# K0N16_Keypad_v1_1.net
KiCad netlist of a schematic drawn in EAGLE
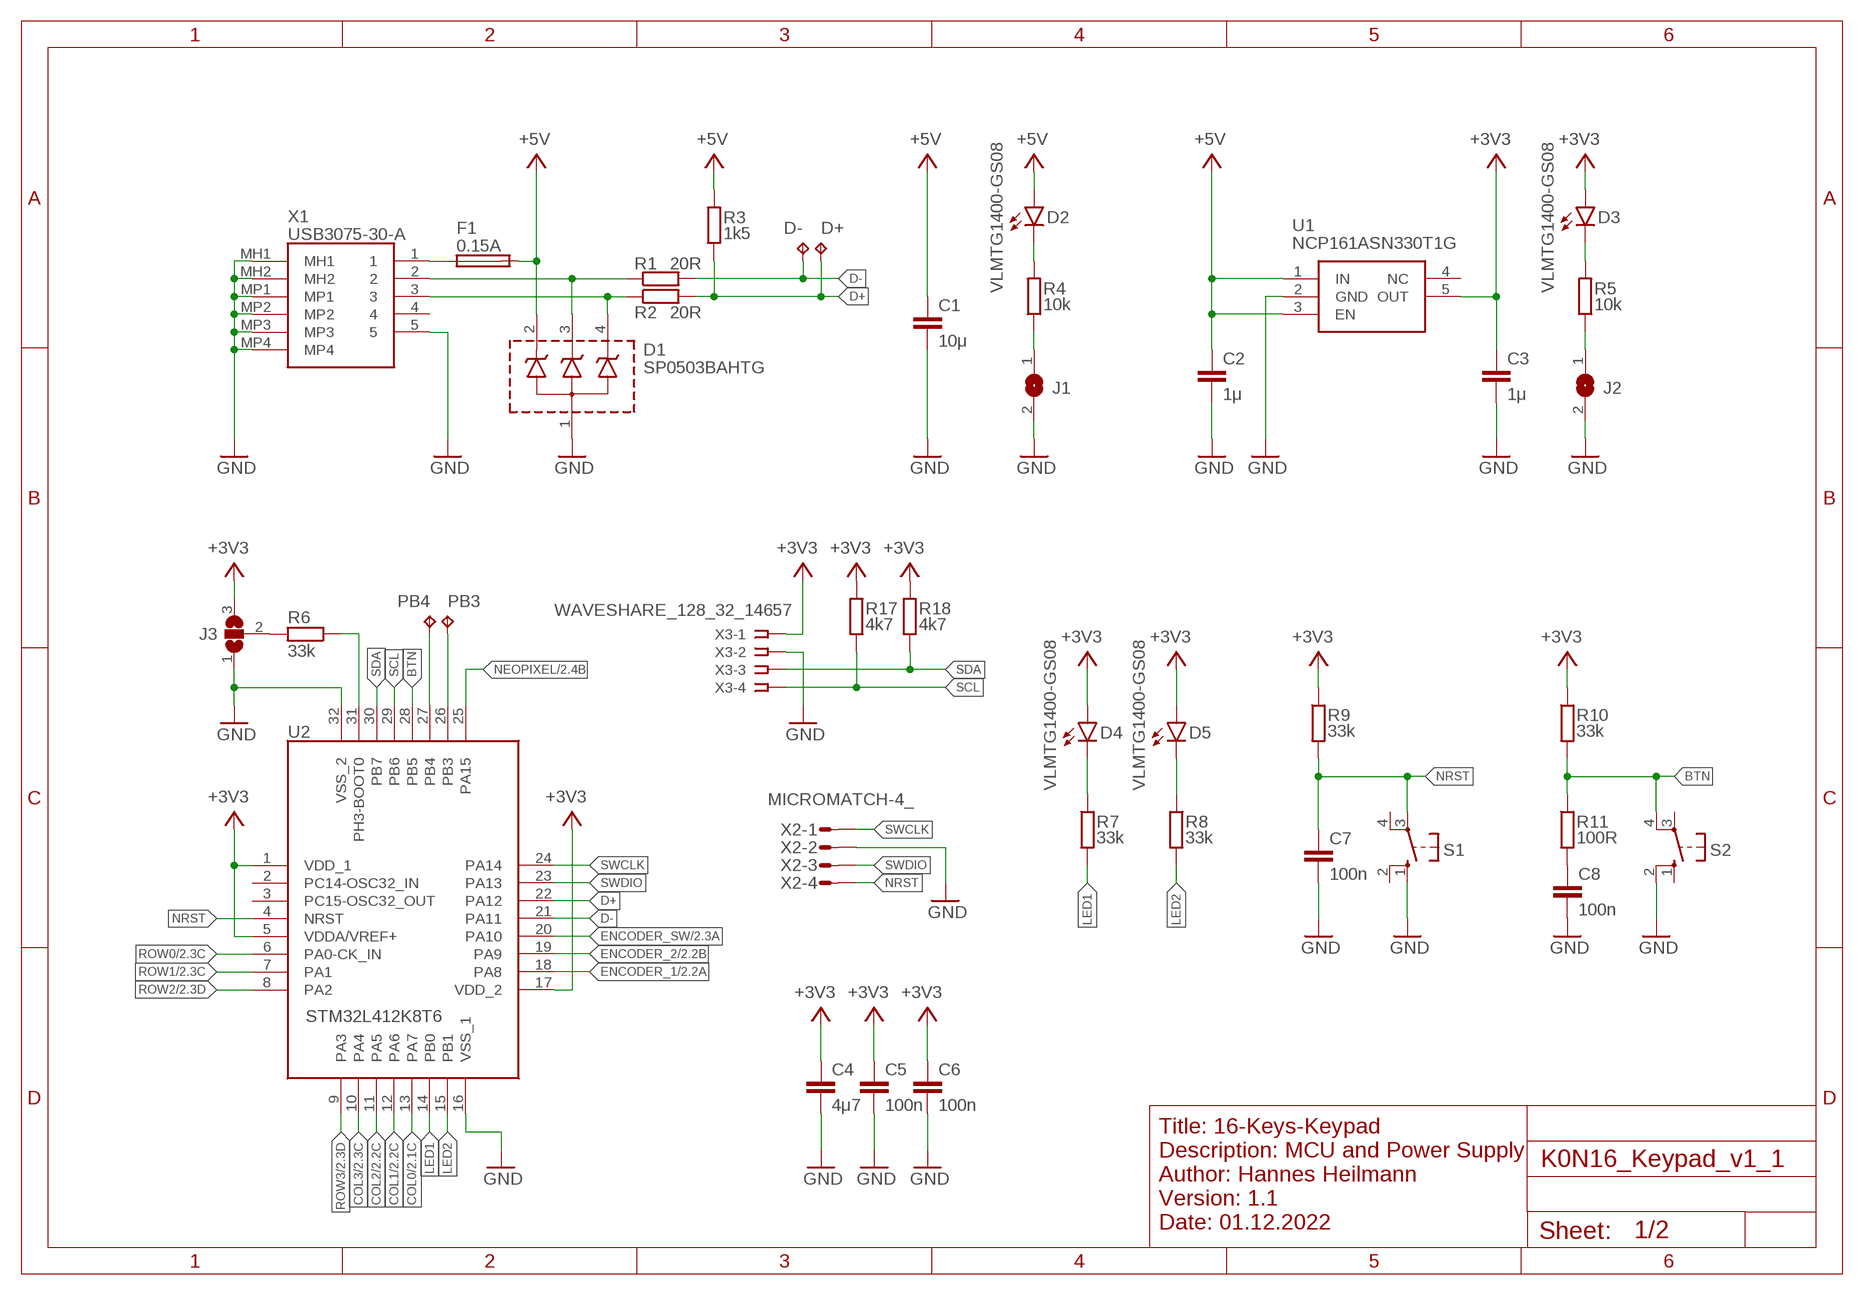
[diagram p0: schematic, sheet 1]
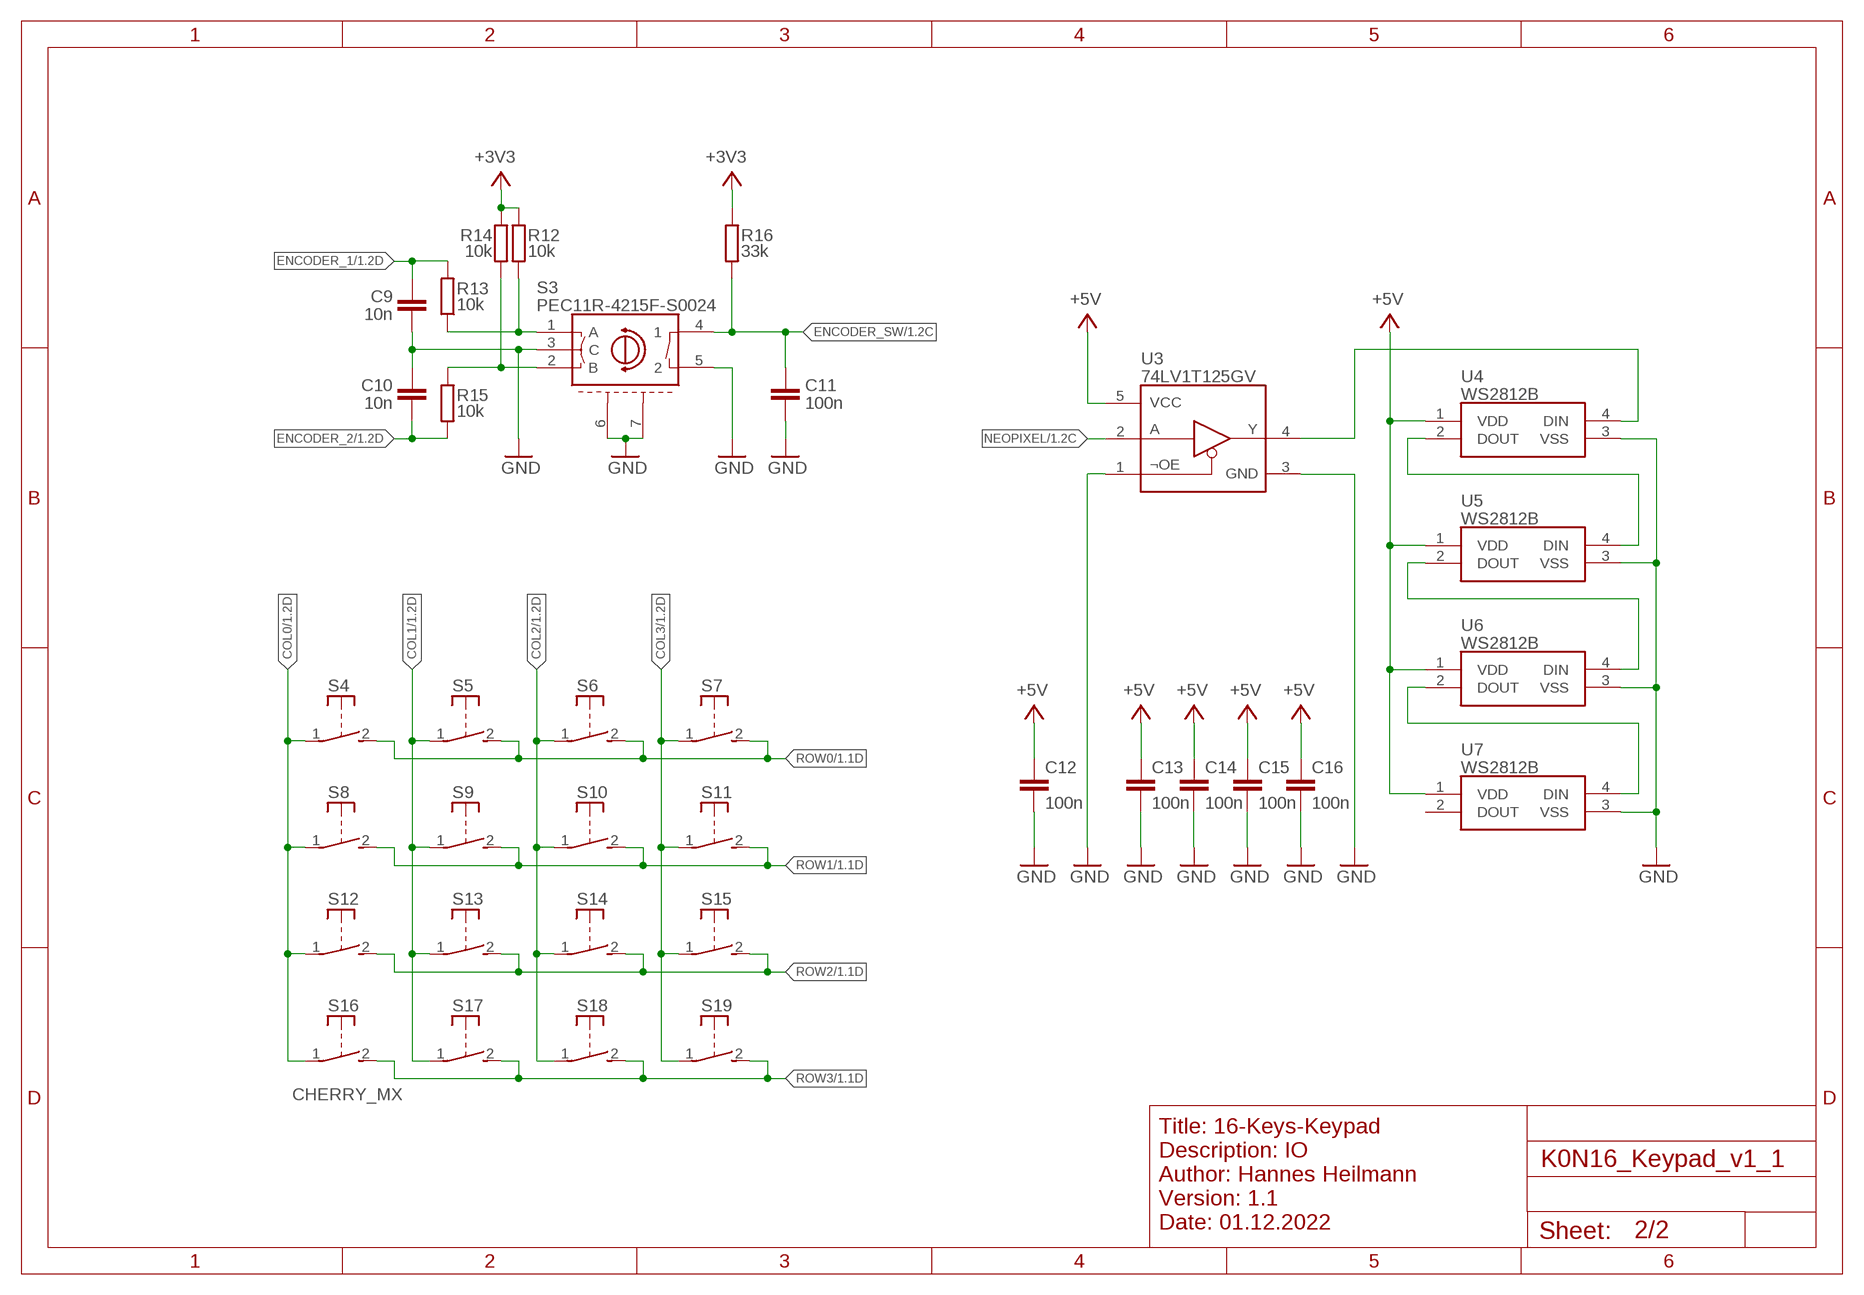
[diagram p1: schematic, sheet 2]

(export (version "E")
  (design (tool "Eeschema 10.0.6"))
  (components
    (comp (ref "C1")
      (value "10μ")
      (footprint "eagle-import:C1206")
      (libsource (lib "eagle-import") (part "C_1206C1206"))
    )
    (comp (ref "C2")
      (value "1μ")
      (footprint "eagle-import:C0805")
      (libsource (lib "eagle-import") (part "C_0805"))
    )
    (comp (ref "C3")
      (value "1μ")
      (footprint "eagle-import:C0805")
      (libsource (lib "eagle-import") (part "C_0805"))
    )
    (comp (ref "C4")
      (value "4μ7")
      (footprint "eagle-import:C0805")
      (libsource (lib "eagle-import") (part "C_0805"))
    )
    (comp (ref "C5")
      (value "100n")
      (footprint "eagle-import:C0805")
      (libsource (lib "eagle-import") (part "C_0805"))
    )
    (comp (ref "C6")
      (value "100n")
      (footprint "eagle-import:C0805")
      (libsource (lib "eagle-import") (part "C_0805"))
    )
    (comp (ref "C7")
      (value "100n")
      (footprint "eagle-import:C0805")
      (libsource (lib "eagle-import") (part "C_0805"))
    )
    (comp (ref "C8")
      (value "100n")
      (footprint "eagle-import:C0805")
      (libsource (lib "eagle-import") (part "C_0805"))
    )
    (comp (ref "D+")
      (value "TPB1,27")
      (footprint "eagle-import:B1,27")
      (libsource (lib "eagle-import") (part "TPB1,27"))
    )
    (comp (ref "D-")
      (value "TPB1,27")
      (footprint "eagle-import:B1,27")
      (libsource (lib "eagle-import") (part "TPB1,27"))
    )
    (comp (ref "D1")
      (value "SP0503BAHTG")
      (footprint "eagle-import:SP0503BAHTG")
      (fields (field (name "MOUSER_PART_NUMBER") "576-SP0503BAHTG"))
      (libsource (lib "eagle-import") (part "SP0503BAHTG"))
    )
    (comp (ref "D2")
      (value "VLMTG1400-GS08")
      (footprint "eagle-import:CHIP-LED0805")
      (libsource (lib "eagle-import") (part "LED_0805"))
    )
    (comp (ref "D3")
      (value "VLMTG1400-GS08")
      (footprint "eagle-import:CHIP-LED0805")
      (libsource (lib "eagle-import") (part "LED_0805"))
    )
    (comp (ref "D4")
      (value "VLMTG1400-GS08")
      (footprint "eagle-import:CHIP-LED0805")
      (libsource (lib "eagle-import") (part "LED_0805"))
    )
    (comp (ref "D5")
      (value "VLMTG1400-GS08")
      (footprint "eagle-import:CHIP-LED0805")
      (libsource (lib "eagle-import") (part "LED_0805"))
    )
    (comp (ref "F1")
      (value "FUSE_0603R0603")
      (footprint "eagle-import:R0603")
      (libsource (lib "eagle-import") (part "FUSE_0603R0603"))
    )
    (comp (ref "J1") (value "SJ") (footprint "eagle-import:SJ") (libsource (lib "eagle-import") (part "SJ")))
    (comp (ref "J2") (value "SJ") (footprint "eagle-import:SJ") (libsource (lib "eagle-import") (part "SJ")))
    (comp (ref "J3")
      (value "SJ2W")
      (footprint "eagle-import:SJ_2")
      (libsource (lib "eagle-import") (part "SJ2W"))
    )
    (comp (ref "PB3")
      (value "TPB1,27")
      (footprint "eagle-import:B1,27")
      (libsource (lib "eagle-import") (part "TPB1,27"))
    )
    (comp (ref "PB4")
      (value "TPB1,27")
      (footprint "eagle-import:B1,27")
      (libsource (lib "eagle-import") (part "TPB1,27"))
    )
    (comp (ref "R1")
      (value "20R")
      (footprint "eagle-import:R0805")
      (libsource (lib "eagle-import") (part "R_0805"))
    )
    (comp (ref "R2")
      (value "20R")
      (footprint "eagle-import:R0805")
      (libsource (lib "eagle-import") (part "R_0805"))
    )
    (comp (ref "R3")
      (value "1k5")
      (footprint "eagle-import:R0805")
      (libsource (lib "eagle-import") (part "R_0805"))
    )
    (comp (ref "R4")
      (value "10k")
      (footprint "eagle-import:R0805")
      (libsource (lib "eagle-import") (part "R_0805"))
    )
    (comp (ref "R5")
      (value "10k")
      (footprint "eagle-import:R0805")
      (libsource (lib "eagle-import") (part "R_0805"))
    )
    (comp (ref "R6")
      (value "33k")
      (footprint "eagle-import:R0805")
      (libsource (lib "eagle-import") (part "R_0805"))
    )
    (comp (ref "R7")
      (value "33k")
      (footprint "eagle-import:R0805")
      (libsource (lib "eagle-import") (part "R_0805"))
    )
    (comp (ref "R8")
      (value "33k")
      (footprint "eagle-import:R0805")
      (libsource (lib "eagle-import") (part "R_0805"))
    )
    (comp (ref "R9")
      (value "33k")
      (footprint "eagle-import:R0805")
      (libsource (lib "eagle-import") (part "R_0805"))
    )
    (comp (ref "R10")
      (value "33k")
      (footprint "eagle-import:R0805")
      (libsource (lib "eagle-import") (part "R_0805"))
    )
    (comp (ref "R11")
      (value "100R")
      (footprint "eagle-import:R0805")
      (libsource (lib "eagle-import") (part "R_0805"))
    )
    (comp (ref "R17")
      (value "4k7")
      (footprint "eagle-import:R0805")
      (libsource (lib "eagle-import") (part "R_0805"))
    )
    (comp (ref "R18")
      (value "4k7")
      (footprint "eagle-import:R0805")
      (libsource (lib "eagle-import") (part "R_0805"))
    )
    (comp (ref "S1")
      (value "10-XXB3F_10XX")
      (footprint "eagle-import:B3F-10XX")
      (libsource (lib "eagle-import") (part "10-XXB3F_10XX"))
    )
    (comp (ref "S2")
      (value "10-XXB3F_10XX")
      (footprint "eagle-import:B3F-10XX")
      (libsource (lib "eagle-import") (part "10-XXB3F_10XX"))
    )
    (comp (ref "U1")
      (value "NCP161ASN330T1G")
      (footprint "eagle-import:SOT95P280X145-5N")
      (fields (field (name "MOUSER_PART_NUMBER") "863-NCP161ASN330T1G"))
      (libsource (lib "eagle-import") (part "NCP161ASN330T1G"))
    )
    (comp (ref "U2")
      (value "STM32L412K8T6")
      (footprint "eagle-import:QFP80P900X900X160-32N")
      (fields (field (name "MOUSER_PART_NUMBER") "511-STM32L412K8T6"))
      (libsource (lib "eagle-import") (part "STM32L412K8T6"))
    )
    (comp (ref "X1")
      (value "USB3075-30-A")
      (footprint "eagle-import:USB307530A")
      (fields (field (name "MOUSER_PART_NUMBER") "640-USB3075-30-A"))
      (libsource (lib "eagle-import") (part "USB3075-30-A"))
    )
    (comp (ref "X2")
      (value "MICROMATCH-4_")
      (footprint "eagle-import:MICROMATCH-4")
      (libsource (lib "eagle-import") (part "MICROMATCH-4_"))
    )
    (comp (ref "X3")
      (value "WAVESHARE_128_32_14657")
      (footprint "eagle-import:SSW-104-02-G-S")
      (fields (field (name "MF") "Samtec Inc.") (field (name "MPN") "SSW-104-02-G-S"))
      (libsource (lib "eagle-import") (part "WAVESHARE_128_32_14657"))
    )
    (comp (ref "C9")
      (value "10n")
      (footprint "eagle-import:C0805")
      (libsource (lib "eagle-import") (part "C_0805"))
    )
    (comp (ref "C10")
      (value "10n")
      (footprint "eagle-import:C0805")
      (libsource (lib "eagle-import") (part "C_0805"))
    )
    (comp (ref "C11")
      (value "100n")
      (footprint "eagle-import:C0805")
      (libsource (lib "eagle-import") (part "C_0805"))
    )
    (comp (ref "C12")
      (value "100n")
      (footprint "eagle-import:C0805")
      (libsource (lib "eagle-import") (part "C_0805"))
    )
    (comp (ref "C13")
      (value "100n")
      (footprint "eagle-import:C0805")
      (libsource (lib "eagle-import") (part "C_0805"))
    )
    (comp (ref "C14")
      (value "100n")
      (footprint "eagle-import:C0805")
      (libsource (lib "eagle-import") (part "C_0805"))
    )
    (comp (ref "C15")
      (value "100n")
      (footprint "eagle-import:C0805")
      (libsource (lib "eagle-import") (part "C_0805"))
    )
    (comp (ref "C16")
      (value "100n")
      (footprint "eagle-import:C0805")
      (libsource (lib "eagle-import") (part "C_0805"))
    )
    (comp (ref "R12")
      (value "10k")
      (footprint "eagle-import:R0805")
      (libsource (lib "eagle-import") (part "R_0805"))
    )
    (comp (ref "R13")
      (value "10k")
      (footprint "eagle-import:R0805")
      (libsource (lib "eagle-import") (part "R_0805"))
    )
    (comp (ref "R14")
      (value "10k")
      (footprint "eagle-import:R0805")
      (libsource (lib "eagle-import") (part "R_0805"))
    )
    (comp (ref "R15")
      (value "10k")
      (footprint "eagle-import:R0805")
      (libsource (lib "eagle-import") (part "R_0805"))
    )
    (comp (ref "R16")
      (value "33k")
      (footprint "eagle-import:R0805")
      (libsource (lib "eagle-import") (part "R_0805"))
    )
    (comp (ref "S3")
      (value "PEC11R-4215F-S0024")
      (footprint "eagle-import:PEC12R-4XXXF-SXXXX_1")
      (fields
        (field (name "ARROW_PART_NUMBER") "PEC11R-4225F-S0024")
        (field (name "MOUSER_PART_NUMBER") "652-PEC11R-4225F-S24")
      )
      (libsource (lib "eagle-import") (part "PEC11R-4215F-S0024"))
    )
    (comp (ref "S4")
      (value "CHERRY_MX")
      (footprint "eagle-import:CHERRY_MX")
      (fields
        (field (name "ARROW_PART_NUMBER") "MX1A-E1NW")
        (field (name "MOUSER_PART_NUMBER") "540-MX1A-E1NW")
      )
      (libsource (lib "eagle-import") (part "CHERRY_MX"))
    )
    (comp (ref "S5")
      (value "CHERRY_MX")
      (footprint "eagle-import:CHERRY_MX")
      (fields
        (field (name "ARROW_PART_NUMBER") "MX1A-E1NW")
        (field (name "MOUSER_PART_NUMBER") "540-MX1A-E1NW")
      )
      (libsource (lib "eagle-import") (part "CHERRY_MX"))
    )
    (comp (ref "S6")
      (value "CHERRY_MX")
      (footprint "eagle-import:CHERRY_MX")
      (fields
        (field (name "ARROW_PART_NUMBER") "MX1A-E1NW")
        (field (name "MOUSER_PART_NUMBER") "540-MX1A-E1NW")
      )
      (libsource (lib "eagle-import") (part "CHERRY_MX"))
    )
    (comp (ref "S7")
      (value "CHERRY_MX")
      (footprint "eagle-import:CHERRY_MX")
      (fields
        (field (name "ARROW_PART_NUMBER") "MX1A-E1NW")
        (field (name "MOUSER_PART_NUMBER") "540-MX1A-E1NW")
      )
      (libsource (lib "eagle-import") (part "CHERRY_MX"))
    )
    (comp (ref "S8")
      (value "CHERRY_MX")
      (footprint "eagle-import:CHERRY_MX")
      (fields
        (field (name "ARROW_PART_NUMBER") "MX1A-E1NW")
        (field (name "MOUSER_PART_NUMBER") "540-MX1A-E1NW")
      )
      (libsource (lib "eagle-import") (part "CHERRY_MX"))
    )
    (comp (ref "S9")
      (value "CHERRY_MX")
      (footprint "eagle-import:CHERRY_MX")
      (fields
        (field (name "ARROW_PART_NUMBER") "MX1A-E1NW")
        (field (name "MOUSER_PART_NUMBER") "540-MX1A-E1NW")
      )
      (libsource (lib "eagle-import") (part "CHERRY_MX"))
    )
    (comp (ref "S10")
      (value "CHERRY_MX")
      (footprint "eagle-import:CHERRY_MX")
      (fields
        (field (name "ARROW_PART_NUMBER") "MX1A-E1NW")
        (field (name "MOUSER_PART_NUMBER") "540-MX1A-E1NW")
      )
      (libsource (lib "eagle-import") (part "CHERRY_MX"))
    )
    (comp (ref "S11")
      (value "CHERRY_MX")
      (footprint "eagle-import:CHERRY_MX")
      (fields
        (field (name "ARROW_PART_NUMBER") "MX1A-E1NW")
        (field (name "MOUSER_PART_NUMBER") "540-MX1A-E1NW")
      )
      (libsource (lib "eagle-import") (part "CHERRY_MX"))
    )
    (comp (ref "S12")
      (value "CHERRY_MX")
      (footprint "eagle-import:CHERRY_MX")
      (fields
        (field (name "ARROW_PART_NUMBER") "MX1A-E1NW")
        (field (name "MOUSER_PART_NUMBER") "540-MX1A-E1NW")
      )
      (libsource (lib "eagle-import") (part "CHERRY_MX"))
    )
    (comp (ref "S13")
      (value "CHERRY_MX")
      (footprint "eagle-import:CHERRY_MX")
      (fields
        (field (name "ARROW_PART_NUMBER") "MX1A-E1NW")
        (field (name "MOUSER_PART_NUMBER") "540-MX1A-E1NW")
      )
      (libsource (lib "eagle-import") (part "CHERRY_MX"))
    )
    (comp (ref "S14")
      (value "CHERRY_MX")
      (footprint "eagle-import:CHERRY_MX")
      (fields
        (field (name "ARROW_PART_NUMBER") "MX1A-E1NW")
        (field (name "MOUSER_PART_NUMBER") "540-MX1A-E1NW")
      )
      (libsource (lib "eagle-import") (part "CHERRY_MX"))
    )
    (comp (ref "S15")
      (value "CHERRY_MX")
      (footprint "eagle-import:CHERRY_MX")
      (fields
        (field (name "ARROW_PART_NUMBER") "MX1A-E1NW")
        (field (name "MOUSER_PART_NUMBER") "540-MX1A-E1NW")
      )
      (libsource (lib "eagle-import") (part "CHERRY_MX"))
    )
    (comp (ref "S16")
      (value "CHERRY_MX")
      (footprint "eagle-import:CHERRY_MX")
      (fields
        (field (name "ARROW_PART_NUMBER") "MX1A-E1NW")
        (field (name "MOUSER_PART_NUMBER") "540-MX1A-E1NW")
      )
      (libsource (lib "eagle-import") (part "CHERRY_MX"))
    )
    (comp (ref "S17")
      (value "CHERRY_MX")
      (footprint "eagle-import:CHERRY_MX")
      (fields
        (field (name "ARROW_PART_NUMBER") "MX1A-E1NW")
        (field (name "MOUSER_PART_NUMBER") "540-MX1A-E1NW")
      )
      (libsource (lib "eagle-import") (part "CHERRY_MX"))
    )
    (comp (ref "S18")
      (value "CHERRY_MX")
      (footprint "eagle-import:CHERRY_MX")
      (fields
        (field (name "ARROW_PART_NUMBER") "MX1A-E1NW")
        (field (name "MOUSER_PART_NUMBER") "540-MX1A-E1NW")
      )
      (libsource (lib "eagle-import") (part "CHERRY_MX"))
    )
    (comp (ref "S19")
      (value "CHERRY_MX")
      (footprint "eagle-import:CHERRY_MX")
      (fields
        (field (name "ARROW_PART_NUMBER") "MX1A-E1NW")
        (field (name "MOUSER_PART_NUMBER") "540-MX1A-E1NW")
      )
      (libsource (lib "eagle-import") (part "CHERRY_MX"))
    )
    (comp (ref "U3")
      (value "74LV1T125GV_")
      (footprint "eagle-import:SOT753")
      (libsource (lib "eagle-import") (part "74LV1T125GV_"))
    )
    (comp (ref "U4")
      (value "WS2812B")
      (footprint "eagle-import:WS2812B")
      (libsource (lib "eagle-import") (part "WS2812B"))
    )
    (comp (ref "U5")
      (value "WS2812B")
      (footprint "eagle-import:WS2812B")
      (libsource (lib "eagle-import") (part "WS2812B"))
    )
    (comp (ref "U6")
      (value "WS2812B")
      (footprint "eagle-import:WS2812B")
      (libsource (lib "eagle-import") (part "WS2812B"))
    )
    (comp (ref "U7")
      (value "WS2812B")
      (footprint "eagle-import:WS2812B")
      (libsource (lib "eagle-import") (part "WS2812B"))
    )
  )
  (nets
    (net (code "1") (name "+3V3") (class "Default")
      (node (ref "C3") (pin "1") (pinfunction "1_1") (pintype "passive"))
      (node (ref "C4") (pin "1") (pinfunction "1_1") (pintype "passive"))
      (node (ref "C5") (pin "1") (pinfunction "1_1") (pintype "passive"))
      (node (ref "C6") (pin "1") (pinfunction "1_1") (pintype "passive"))
      (node (ref "D3") (pin "A") (pinfunction "A_A") (pintype "passive"))
      (node (ref "D4") (pin "A") (pinfunction "A_A") (pintype "passive"))
      (node (ref "D5") (pin "A") (pinfunction "A_A") (pintype "passive"))
      (node (ref "J3") (pin "3") (pinfunction "3_3") (pintype "passive"))
      (node (ref "R10") (pin "1") (pinfunction "1_1") (pintype "passive"))
      (node (ref "R12") (pin "1") (pinfunction "1_1") (pintype "passive"))
      (node (ref "R14") (pin "1") (pinfunction "1_1") (pintype "passive"))
      (node (ref "R16") (pin "1") (pinfunction "1_1") (pintype "passive"))
      (node (ref "R17") (pin "1") (pinfunction "1_1") (pintype "passive"))
      (node (ref "R18") (pin "1") (pinfunction "1_1") (pintype "passive"))
      (node (ref "R9") (pin "1") (pinfunction "1_1") (pintype "passive"))
      (node (ref "U1") (pin "5") (pinfunction "OUT_5") (pintype "bidirectional"))
      (node (ref "U2") (pin "1") (pinfunction "VDD_1_1") (pintype "bidirectional"))
      (node (ref "U2") (pin "17") (pinfunction "VDD_2_17") (pintype "bidirectional"))
      (node (ref "U2") (pin "5") (pinfunction "VDDA/VREF+_5") (pintype "bidirectional"))
      (node (ref "X3") (pin "1") (pinfunction "1_1") (pintype "passive"))
    )
    (net (code "2") (name "+5V") (class "Default")
      (node (ref "C1") (pin "1") (pinfunction "1_1") (pintype "passive"))
      (node (ref "C12") (pin "1") (pinfunction "1_1") (pintype "passive"))
      (node (ref "C13") (pin "1") (pinfunction "1_1") (pintype "passive"))
      (node (ref "C14") (pin "1") (pinfunction "1_1") (pintype "passive"))
      (node (ref "C15") (pin "1") (pinfunction "1_1") (pintype "passive"))
      (node (ref "C16") (pin "1") (pinfunction "1_1") (pintype "passive"))
      (node (ref "C2") (pin "1") (pinfunction "1_1") (pintype "passive"))
      (node (ref "D1") (pin "2") (pinfunction "K_1_2") (pintype "bidirectional"))
      (node (ref "D2") (pin "A") (pinfunction "A_A") (pintype "passive"))
      (node (ref "F1") (pin "2") (pinfunction "2_2") (pintype "passive"))
      (node (ref "R3") (pin "2") (pinfunction "2_2") (pintype "passive"))
      (node (ref "U1") (pin "1") (pinfunction "IN_1") (pintype "bidirectional"))
      (node (ref "U1") (pin "3") (pinfunction "EN_3") (pintype "bidirectional"))
      (node (ref "U3") (pin "5") (pinfunction "VCC_5") (pintype "bidirectional"))
      (node (ref "U4") (pin "1") (pinfunction "VDD_1") (pintype "bidirectional"))
      (node (ref "U5") (pin "1") (pinfunction "VDD_1") (pintype "bidirectional"))
      (node (ref "U6") (pin "1") (pinfunction "VDD_1") (pintype "bidirectional"))
      (node (ref "U7") (pin "1") (pinfunction "VDD_1") (pintype "bidirectional"))
    )
    (net (code "3") (name "BTN") (class "Default")
      (node (ref "R10") (pin "2") (pinfunction "2_2") (pintype "passive"))
      (node (ref "R11") (pin "1") (pinfunction "1_1") (pintype "passive"))
      (node (ref "S2") (pin "4") (pinfunction "P1_4") (pintype "passive"))
      (node (ref "U2") (pin "28") (pinfunction "PB5_28") (pintype "bidirectional"))
    )
    (net (code "4") (name "COL0") (class "Default")
      (node (ref "S12") (pin "1") (pinfunction "P_1") (pintype "passive"))
      (node (ref "S16") (pin "1") (pinfunction "P_1") (pintype "passive"))
      (node (ref "S4") (pin "1") (pinfunction "P_1") (pintype "passive"))
      (node (ref "S8") (pin "1") (pinfunction "P_1") (pintype "passive"))
      (node (ref "U2") (pin "13") (pinfunction "PA7_13") (pintype "bidirectional"))
    )
    (net (code "5") (name "COL1") (class "Default")
      (node (ref "S13") (pin "1") (pinfunction "P_1") (pintype "passive"))
      (node (ref "S17") (pin "1") (pinfunction "P_1") (pintype "passive"))
      (node (ref "S5") (pin "1") (pinfunction "P_1") (pintype "passive"))
      (node (ref "S9") (pin "1") (pinfunction "P_1") (pintype "passive"))
      (node (ref "U2") (pin "12") (pinfunction "PA6_12") (pintype "bidirectional"))
    )
    (net (code "6") (name "COL2") (class "Default")
      (node (ref "S10") (pin "1") (pinfunction "P_1") (pintype "passive"))
      (node (ref "S14") (pin "1") (pinfunction "P_1") (pintype "passive"))
      (node (ref "S18") (pin "1") (pinfunction "P_1") (pintype "passive"))
      (node (ref "S6") (pin "1") (pinfunction "P_1") (pintype "passive"))
      (node (ref "U2") (pin "11") (pinfunction "PA5_11") (pintype "bidirectional"))
    )
    (net (code "7") (name "COL3") (class "Default")
      (node (ref "S11") (pin "1") (pinfunction "P_1") (pintype "passive"))
      (node (ref "S15") (pin "1") (pinfunction "P_1") (pintype "passive"))
      (node (ref "S19") (pin "1") (pinfunction "P_1") (pintype "passive"))
      (node (ref "S7") (pin "1") (pinfunction "P_1") (pintype "passive"))
      (node (ref "U2") (pin "10") (pinfunction "PA4_10") (pintype "bidirectional"))
    )
    (net (code "8") (name "D+") (class "Default")
      (node (ref "D+") (pin "TP") (pinfunction "TP_TP") (pintype "input"))
      (node (ref "R2") (pin "2") (pinfunction "2_2") (pintype "passive"))
      (node (ref "R3") (pin "1") (pinfunction "1_1") (pintype "passive"))
      (node (ref "U2") (pin "22") (pinfunction "PA12_22") (pintype "bidirectional"))
    )
    (net (code "9") (name "D-") (class "Default")
      (node (ref "D-") (pin "TP") (pinfunction "TP_TP") (pintype "input"))
      (node (ref "R1") (pin "2") (pinfunction "2_2") (pintype "passive"))
      (node (ref "U2") (pin "21") (pinfunction "PA11_21") (pintype "bidirectional"))
    )
    (net (code "10") (name "ENCODER_1") (class "Default")
      (node (ref "C9") (pin "1") (pinfunction "1_1") (pintype "passive"))
      (node (ref "R13") (pin "2") (pinfunction "2_2") (pintype "passive"))
      (node (ref "U2") (pin "18") (pinfunction "PA8_18") (pintype "bidirectional"))
    )
    (net (code "11") (name "ENCODER_2") (class "Default")
      (node (ref "C10") (pin "2") (pinfunction "2_2") (pintype "passive"))
      (node (ref "R15") (pin "2") (pinfunction "2_2") (pintype "passive"))
      (node (ref "U2") (pin "19") (pinfunction "PA9_19") (pintype "bidirectional"))
    )
    (net (code "12") (name "ENCODER_SW") (class "Default")
      (node (ref "C11") (pin "1") (pinfunction "1_1") (pintype "passive"))
      (node (ref "R16") (pin "2") (pinfunction "2_2") (pintype "passive"))
      (node (ref "S3") (pin "4") (pinfunction "1_4") (pintype "bidirectional"))
      (node (ref "U2") (pin "20") (pinfunction "PA10_20") (pintype "bidirectional"))
    )
    (net (code "13") (name "GND") (class "Default")
      (node (ref "C1") (pin "2") (pinfunction "2_2") (pintype "passive"))
      (node (ref "C10") (pin "1") (pinfunction "1_1") (pintype "passive"))
      (node (ref "C11") (pin "2") (pinfunction "2_2") (pintype "passive"))
      (node (ref "C12") (pin "2") (pinfunction "2_2") (pintype "passive"))
      (node (ref "C13") (pin "2") (pinfunction "2_2") (pintype "passive"))
      (node (ref "C14") (pin "2") (pinfunction "2_2") (pintype "passive"))
      (node (ref "C15") (pin "2") (pinfunction "2_2") (pintype "passive"))
      (node (ref "C16") (pin "2") (pinfunction "2_2") (pintype "passive"))
      (node (ref "C2") (pin "2") (pinfunction "2_2") (pintype "passive"))
      (node (ref "C3") (pin "2") (pinfunction "2_2") (pintype "passive"))
      (node (ref "C4") (pin "2") (pinfunction "2_2") (pintype "passive"))
      (node (ref "C5") (pin "2") (pinfunction "2_2") (pintype "passive"))
      (node (ref "C6") (pin "2") (pinfunction "2_2") (pintype "passive"))
      (node (ref "C7") (pin "2") (pinfunction "2_2") (pintype "passive"))
      (node (ref "C8") (pin "2") (pinfunction "2_2") (pintype "passive"))
      (node (ref "C9") (pin "2") (pinfunction "2_2") (pintype "passive"))
      (node (ref "D1") (pin "1") (pinfunction "COMMON_A_1") (pintype "bidirectional"))
      (node (ref "J1") (pin "2") (pinfunction "2_2") (pintype "passive"))
      (node (ref "J2") (pin "2") (pinfunction "2_2") (pintype "passive"))
      (node (ref "J3") (pin "1") (pinfunction "1_1") (pintype "passive"))
      (node (ref "S1") (pin "1") (pinfunction "S_1") (pintype "passive"))
      (node (ref "S2") (pin "2") (pinfunction "S1_2") (pintype "passive"))
      (node (ref "S3") (pin "3") (pinfunction "C_3") (pintype "bidirectional"))
      (node (ref "S3") (pin "5") (pinfunction "2_5") (pintype "bidirectional"))
      (node (ref "S3") (pin "6") (pinfunction "GND1_6") (pintype "bidirectional"))
      (node (ref "S3") (pin "7") (pinfunction "GND2_7") (pintype "bidirectional"))
      (node (ref "U1") (pin "2") (pinfunction "GND_2") (pintype "power_in"))
      (node (ref "U2") (pin "16") (pinfunction "VSS_1_16") (pintype "bidirectional"))
      (node (ref "U2") (pin "32") (pinfunction "VSS_2_32") (pintype "bidirectional"))
      (node (ref "U3") (pin "1") (pinfunction "¬OE_1") (pintype "bidirectional"))
      (node (ref "U3") (pin "3") (pinfunction "GND_3") (pintype "bidirectional"))
      (node (ref "U4") (pin "3") (pinfunction "VSS_3") (pintype "bidirectional"))
      (node (ref "U5") (pin "3") (pinfunction "VSS_3") (pintype "bidirectional"))
      (node (ref "U6") (pin "3") (pinfunction "VSS_3") (pintype "bidirectional"))
      (node (ref "U7") (pin "3") (pinfunction "VSS_3") (pintype "bidirectional"))
      (node (ref "X1") (pin "5") (pinfunction "5_5") (pintype "bidirectional"))
      (node (ref "X1") (pin "MH1") (pinfunction "MH1_MH1") (pintype "bidirectional"))
      (node (ref "X1") (pin "MH2") (pinfunction "MH2_MH2") (pintype "bidirectional"))
      (node (ref "X1") (pin "MP1") (pinfunction "MP1_MP1") (pintype "bidirectional"))
      (node (ref "X1") (pin "MP2") (pinfunction "MP2_MP2") (pintype "bidirectional"))
      (node (ref "X1") (pin "MP3") (pinfunction "MP3_MP3") (pintype "bidirectional"))
      (node (ref "X1") (pin "MP4") (pinfunction "MP4_MP4") (pintype "bidirectional"))
      (node (ref "X2") (pin "2") (pinfunction "S_2") (pintype "passive"))
      (node (ref "X3") (pin "2") (pinfunction "1_2") (pintype "passive"))
    )
    (net (code "14") (name "LED1") (class "Default")
      (node (ref "R7") (pin "2") (pinfunction "2_2") (pintype "passive"))
      (node (ref "U2") (pin "14") (pinfunction "PB0_14") (pintype "bidirectional"))
    )
    (net (code "15") (name "LED2") (class "Default")
      (node (ref "R8") (pin "2") (pinfunction "2_2") (pintype "passive"))
      (node (ref "U2") (pin "15") (pinfunction "PB1_15") (pintype "bidirectional"))
    )
    (net (code "16") (name "NEOPIXEL") (class "Default")
      (node (ref "U2") (pin "25") (pinfunction "PA15_25") (pintype "bidirectional"))
      (node (ref "U3") (pin "2") (pinfunction "A_2") (pintype "bidirectional"))
    )
    (net (code "17") (name "NRST") (class "Default")
      (node (ref "C7") (pin "1") (pinfunction "1_1") (pintype "passive"))
      (node (ref "R9") (pin "2") (pinfunction "2_2") (pintype "passive"))
      (node (ref "S1") (pin "3") (pinfunction "P_3") (pintype "passive"))
      (node (ref "U2") (pin "4") (pinfunction "NRST_4") (pintype "bidirectional"))
      (node (ref "X2") (pin "4") (pinfunction "S_4") (pintype "passive"))
    )
    (net (code "18") (name "Net-(C8-Pad1)") (class "Default")
      (node (ref "C8") (pin "1") (pinfunction "1_1") (pintype "passive"))
      (node (ref "R11") (pin "2") (pinfunction "2_2") (pintype "passive"))
    )
    (net (code "19") (name "Net-(D1-K_2)") (class "Default")
      (node (ref "D1") (pin "3") (pinfunction "K_2_3") (pintype "bidirectional"))
      (node (ref "R1") (pin "1") (pinfunction "1_1") (pintype "passive"))
      (node (ref "X1") (pin "2") (pinfunction "2_2") (pintype "bidirectional"))
    )
    (net (code "20") (name "Net-(D1-K_3)") (class "Default")
      (node (ref "D1") (pin "4") (pinfunction "K_3_4") (pintype "bidirectional"))
      (node (ref "R2") (pin "1") (pinfunction "1_1") (pintype "passive"))
      (node (ref "X1") (pin "3") (pinfunction "3_3") (pintype "bidirectional"))
    )
    (net (code "21") (name "Net-(D2-PadC)") (class "Default")
      (node (ref "D2") (pin "C") (pinfunction "C_C") (pintype "passive"))
      (node (ref "R4") (pin "2") (pinfunction "2_2") (pintype "passive"))
    )
    (net (code "22") (name "Net-(D3-PadC)") (class "Default")
      (node (ref "D3") (pin "C") (pinfunction "C_C") (pintype "passive"))
      (node (ref "R5") (pin "2") (pinfunction "2_2") (pintype "passive"))
    )
    (net (code "23") (name "Net-(D4-PadC)") (class "Default")
      (node (ref "D4") (pin "C") (pinfunction "C_C") (pintype "passive"))
      (node (ref "R7") (pin "1") (pinfunction "1_1") (pintype "passive"))
    )
    (net (code "24") (name "Net-(D5-PadC)") (class "Default")
      (node (ref "D5") (pin "C") (pinfunction "C_C") (pintype "passive"))
      (node (ref "R8") (pin "1") (pinfunction "1_1") (pintype "passive"))
    )
    (net (code "25") (name "Net-(F1-Pad1)") (class "Default")
      (node (ref "F1") (pin "1") (pinfunction "1_1") (pintype "passive"))
      (node (ref "X1") (pin "1") (pinfunction "1_1") (pintype "bidirectional"))
    )
    (net (code "26") (name "Net-(J1-Pad1)") (class "Default")
      (node (ref "J1") (pin "1") (pinfunction "1_1") (pintype "passive"))
      (node (ref "R4") (pin "1") (pinfunction "1_1") (pintype "passive"))
    )
    (net (code "27") (name "Net-(J2-Pad1)") (class "Default")
      (node (ref "J2") (pin "1") (pinfunction "1_1") (pintype "passive"))
      (node (ref "R5") (pin "1") (pinfunction "1_1") (pintype "passive"))
    )
    (net (code "28") (name "Net-(J3-Pad2)") (class "Default")
      (node (ref "J3") (pin "2") (pinfunction "2_2") (pintype "passive"))
      (node (ref "R6") (pin "2") (pinfunction "2_2") (pintype "passive"))
    )
    (net (code "29") (name "Net-(S3-A)") (class "Default")
      (node (ref "R12") (pin "2") (pinfunction "2_2") (pintype "passive"))
      (node (ref "R13") (pin "1") (pinfunction "1_1") (pintype "passive"))
      (node (ref "S3") (pin "1") (pinfunction "A_1") (pintype "bidirectional"))
    )
    (net (code "30") (name "Net-(S3-B)") (class "Default")
      (node (ref "R14") (pin "2") (pinfunction "2_2") (pintype "passive"))
      (node (ref "R15") (pin "1") (pinfunction "1_1") (pintype "passive"))
      (node (ref "S3") (pin "2") (pinfunction "B_2") (pintype "bidirectional"))
    )
    (net (code "31") (name "Net-(U2-PB3)") (class "Default")
      (node (ref "PB3") (pin "TP") (pinfunction "TP_TP") (pintype "input"))
      (node (ref "U2") (pin "26") (pinfunction "PB3_26") (pintype "bidirectional"))
    )
    (net (code "32") (name "Net-(U2-PB4)") (class "Default")
      (node (ref "PB4") (pin "TP") (pinfunction "TP_TP") (pintype "input"))
      (node (ref "U2") (pin "27") (pinfunction "PB4_27") (pintype "bidirectional"))
    )
    (net (code "33") (name "Net-(U2-PH3-BOOT0)") (class "Default")
      (node (ref "R6") (pin "1") (pinfunction "1_1") (pintype "passive"))
      (node (ref "U2") (pin "31") (pinfunction "PH3-BOOT0_31") (pintype "bidirectional"))
    )
    (net (code "34") (name "Net-(U3-Y)") (class "Default")
      (node (ref "U3") (pin "4") (pinfunction "Y_4") (pintype "bidirectional"))
      (node (ref "U4") (pin "4") (pinfunction "DIN_4") (pintype "bidirectional"))
    )
    (net (code "35") (name "Net-(U4-DOUT)") (class "Default")
      (node (ref "U4") (pin "2") (pinfunction "DOUT_2") (pintype "bidirectional"))
      (node (ref "U5") (pin "4") (pinfunction "DIN_4") (pintype "bidirectional"))
    )
    (net (code "36") (name "Net-(U5-DOUT)") (class "Default")
      (node (ref "U5") (pin "2") (pinfunction "DOUT_2") (pintype "bidirectional"))
      (node (ref "U6") (pin "4") (pinfunction "DIN_4") (pintype "bidirectional"))
    )
    (net (code "37") (name "Net-(U6-DOUT)") (class "Default")
      (node (ref "U6") (pin "2") (pinfunction "DOUT_2") (pintype "bidirectional"))
      (node (ref "U7") (pin "4") (pinfunction "DIN_4") (pintype "bidirectional"))
    )
    (net (code "38") (name "ROW0") (class "Default")
      (node (ref "S4") (pin "2") (pinfunction "S_2") (pintype "passive"))
      (node (ref "S5") (pin "2") (pinfunction "S_2") (pintype "passive"))
      (node (ref "S6") (pin "2") (pinfunction "S_2") (pintype "passive"))
      (node (ref "S7") (pin "2") (pinfunction "S_2") (pintype "passive"))
      (node (ref "U2") (pin "6") (pinfunction "PA0-CK_IN_6") (pintype "bidirectional"))
    )
    (net (code "39") (name "ROW1") (class "Default")
      (node (ref "S10") (pin "2") (pinfunction "S_2") (pintype "passive"))
      (node (ref "S11") (pin "2") (pinfunction "S_2") (pintype "passive"))
      (node (ref "S8") (pin "2") (pinfunction "S_2") (pintype "passive"))
      (node (ref "S9") (pin "2") (pinfunction "S_2") (pintype "passive"))
      (node (ref "U2") (pin "7") (pinfunction "PA1_7") (pintype "bidirectional"))
    )
    (net (code "40") (name "ROW2") (class "Default")
      (node (ref "S12") (pin "2") (pinfunction "S_2") (pintype "passive"))
      (node (ref "S13") (pin "2") (pinfunction "S_2") (pintype "passive"))
      (node (ref "S14") (pin "2") (pinfunction "S_2") (pintype "passive"))
      (node (ref "S15") (pin "2") (pinfunction "S_2") (pintype "passive"))
      (node (ref "U2") (pin "8") (pinfunction "PA2_8") (pintype "bidirectional"))
    )
    (net (code "41") (name "ROW3") (class "Default")
      (node (ref "S16") (pin "2") (pinfunction "S_2") (pintype "passive"))
      (node (ref "S17") (pin "2") (pinfunction "S_2") (pintype "passive"))
      (node (ref "S18") (pin "2") (pinfunction "S_2") (pintype "passive"))
      (node (ref "S19") (pin "2") (pinfunction "S_2") (pintype "passive"))
      (node (ref "U2") (pin "9") (pinfunction "PA3_9") (pintype "bidirectional"))
    )
    (net (code "42") (name "SCL") (class "Default")
      (node (ref "R17") (pin "2") (pinfunction "2_2") (pintype "passive"))
      (node (ref "U2") (pin "29") (pinfunction "PB6_29") (pintype "bidirectional"))
      (node (ref "X3") (pin "4") (pinfunction "1_4") (pintype "passive"))
    )
    (net (code "43") (name "SDA") (class "Default")
      (node (ref "R18") (pin "2") (pinfunction "2_2") (pintype "passive"))
      (node (ref "U2") (pin "30") (pinfunction "PB7_30") (pintype "bidirectional"))
      (node (ref "X3") (pin "3") (pinfunction "1_3") (pintype "passive"))
    )
    (net (code "44") (name "SWCLK") (class "Default")
      (node (ref "U2") (pin "24") (pinfunction "PA14_24") (pintype "bidirectional"))
      (node (ref "X2") (pin "1") (pinfunction "S_1") (pintype "passive"))
    )
    (net (code "45") (name "SWDIO") (class "Default")
      (node (ref "U2") (pin "23") (pinfunction "PA13_23") (pintype "bidirectional"))
      (node (ref "X2") (pin "3") (pinfunction "S_3") (pintype "passive"))
    )
    (net (code "46") (name "unconnected-(S1-P1-Pad4)") (class "Default")
      (node (ref "S1") (pin "4") (pinfunction "P1_4") (pintype "passive"))
    )
    (net (code "47") (name "unconnected-(S1-S1-Pad2)") (class "Default")
      (node (ref "S1") (pin "2") (pinfunction "S1_2") (pintype "passive"))
    )
    (net (code "48") (name "unconnected-(S2-P-Pad3)") (class "Default")
      (node (ref "S2") (pin "3") (pinfunction "P_3") (pintype "passive"))
    )
    (net (code "49") (name "unconnected-(S2-S-Pad1)") (class "Default")
      (node (ref "S2") (pin "1") (pinfunction "S_1") (pintype "passive"))
    )
    (net (code "50") (name "unconnected-(U1-NC-Pad4)") (class "Default")
      (node (ref "U1") (pin "4") (pinfunction "NC_4") (pintype "no_connect"))
    )
    (net (code "51") (name "unconnected-(U2-PC14-OSC32_IN-Pad2)") (class "Default")
      (node (ref "U2") (pin "2") (pinfunction "PC14-OSC32_IN_2") (pintype "bidirectional"))
    )
    (net (code "52") (name "unconnected-(U2-PC15-OSC32_OUT-Pad3)") (class "Default")
      (node (ref "U2") (pin "3") (pinfunction "PC15-OSC32_OUT_3") (pintype "bidirectional"))
    )
    (net (code "53") (name "unconnected-(U7-DOUT-Pad2)") (class "Default")
      (node (ref "U7") (pin "2") (pinfunction "DOUT_2") (pintype "bidirectional"))
    )
    (net (code "54") (name "unconnected-(X1-Pad4)") (class "Default")
      (node (ref "X1") (pin "4") (pinfunction "4_4") (pintype "bidirectional"))
    )
  )
)
